# dac-shield.net
KiCad netlist of a schematic drawn in EAGLE
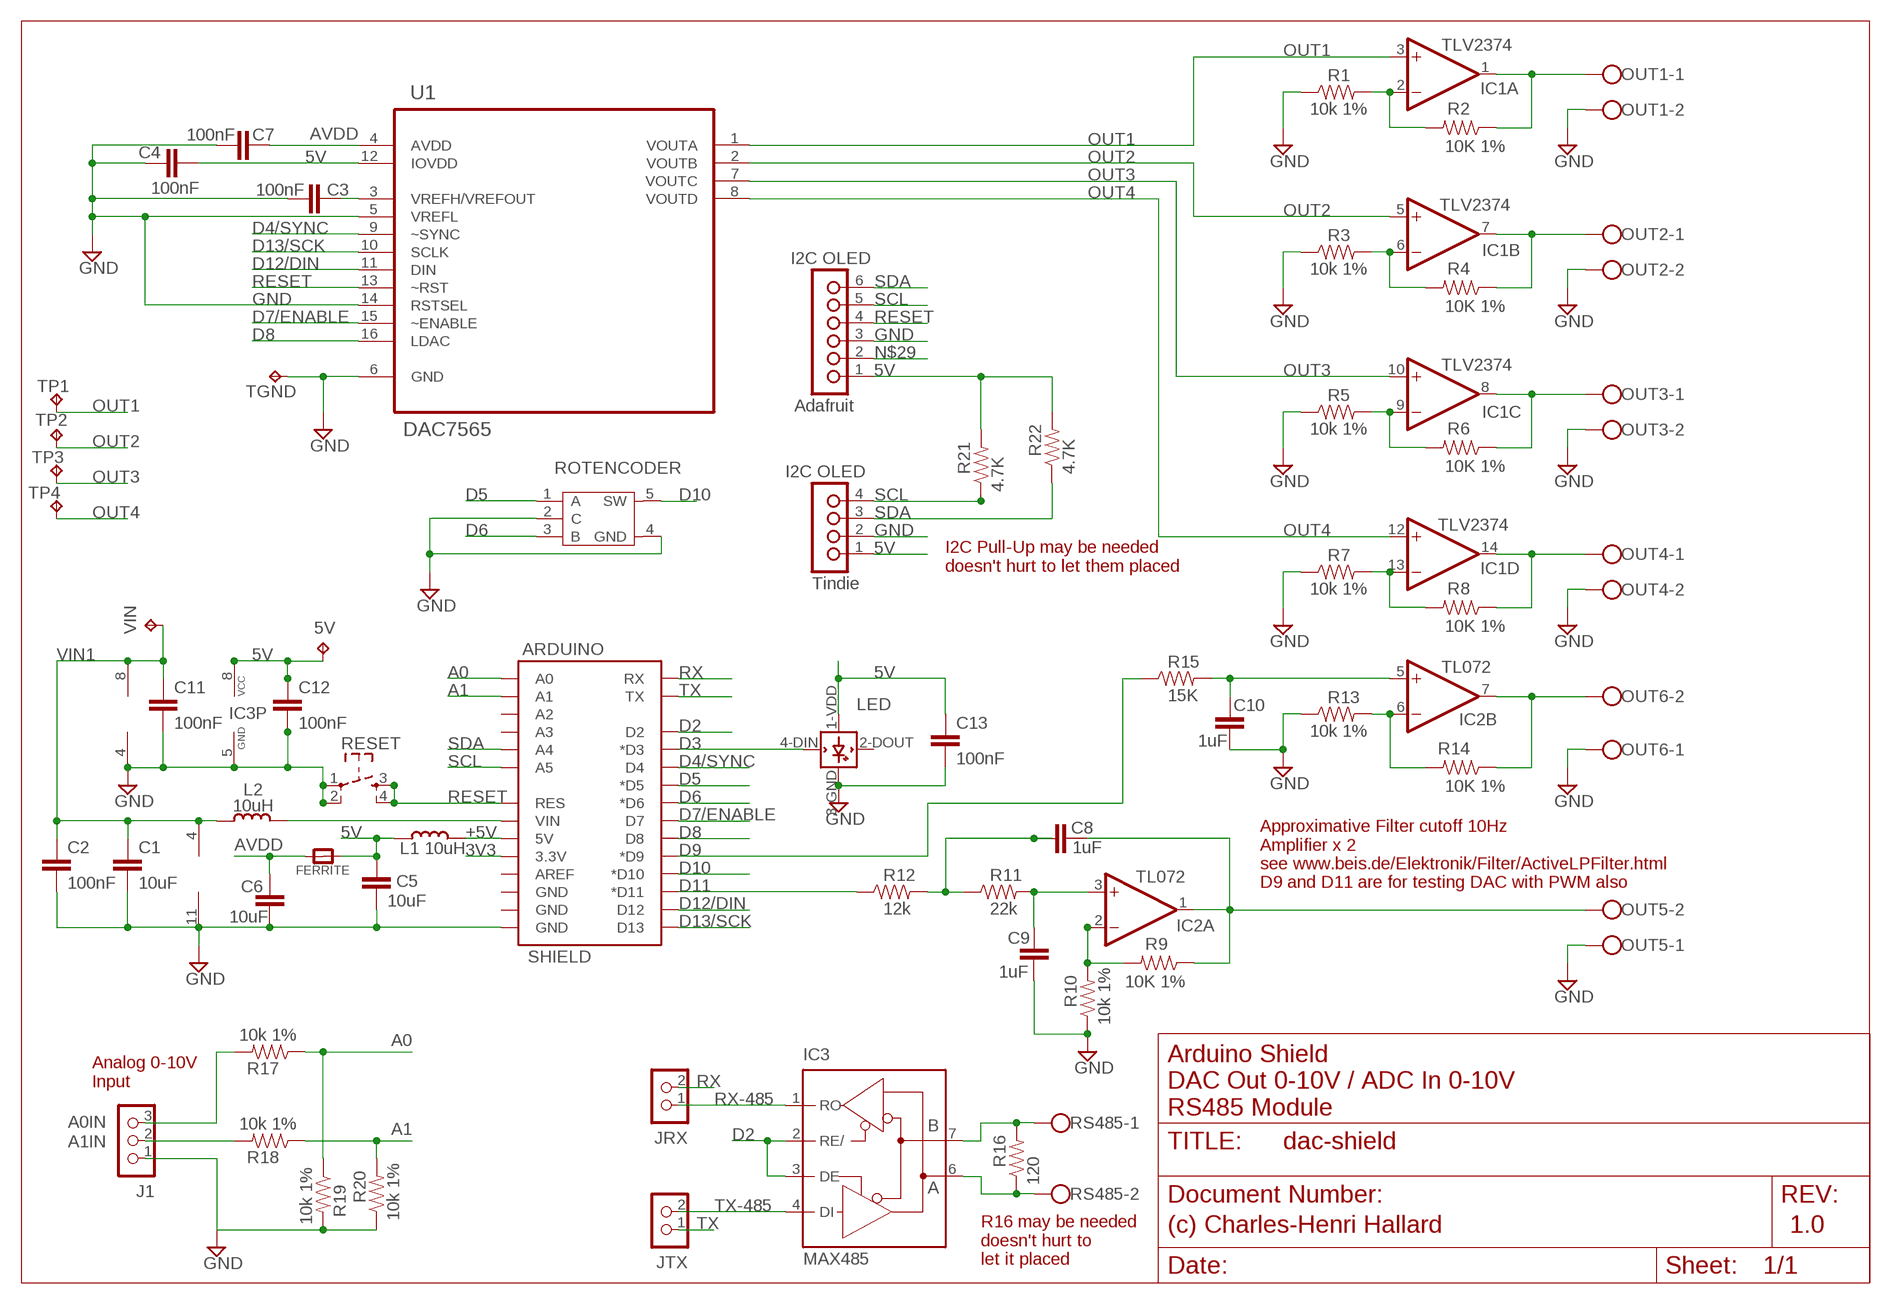
[diagram p0: schematic, sheet 1]

(export (version "E")
  (design (tool "Eeschema 10.0.6"))
  (components
    (comp (ref "5V")
      (value "TPPAD1-13")
      (footprint "eagle-import:P1-13")
      (libsource (lib "eagle-import") (part "TPPAD1-13"))
    )
    (comp (ref "ARDUINO")
      (value "SHIELD")
      (footprint "eagle-import:DUEMILANOVE_SHIELD_NOHOLES")
      (libsource (lib "eagle-import") (part "ARDUINO_SHIELDNOHOLES"))
    )
    (comp (ref "C1")
      (value "10uF")
      (footprint "eagle-import:0805-CAP")
      (libsource (lib "eagle-import") (part "CAP0805-CAP"))
    )
    (comp (ref "C2")
      (value "100nF")
      (footprint "eagle-import:0805-CAP")
      (libsource (lib "eagle-import") (part "CAP0805-CAP"))
    )
    (comp (ref "C3")
      (value "100nF")
      (footprint "eagle-import:0805-CAP")
      (libsource (lib "eagle-import") (part "CAP0805-CAP"))
    )
    (comp (ref "C4")
      (value "100nF")
      (footprint "eagle-import:0805-CAP")
      (libsource (lib "eagle-import") (part "CAP0805-CAP"))
    )
    (comp (ref "C5")
      (value "10uF")
      (footprint "eagle-import:0805-CAP")
      (libsource (lib "eagle-import") (part "CAP0805-CAP"))
    )
    (comp (ref "C6")
      (value "10uF")
      (footprint "eagle-import:0805-CAP")
      (libsource (lib "eagle-import") (part "CAP0805-CAP"))
    )
    (comp (ref "C7")
      (value "100nF")
      (footprint "eagle-import:0805-CAP")
      (libsource (lib "eagle-import") (part "CAP0805-CAP"))
    )
    (comp (ref "C8")
      (value "1uF")
      (footprint "eagle-import:0805-CAP")
      (libsource (lib "eagle-import") (part "CAP0805-CAP"))
    )
    (comp (ref "C9")
      (value "1uF")
      (footprint "eagle-import:0805-CAP")
      (libsource (lib "eagle-import") (part "CAP0805-CAP"))
    )
    (comp (ref "C10")
      (value "1uF")
      (footprint "eagle-import:0805-CAP")
      (libsource (lib "eagle-import") (part "CAP0805-CAP"))
    )
    (comp (ref "C11")
      (value "100nF")
      (footprint "eagle-import:0805-CAP")
      (libsource (lib "eagle-import") (part "CAP0805-CAP"))
    )
    (comp (ref "C12")
      (value "100nF")
      (footprint "eagle-import:0805-CAP")
      (libsource (lib "eagle-import") (part "CAP0805-CAP"))
    )
    (comp (ref "C13")
      (value "100nF")
      (footprint "eagle-import:0805-CAP")
      (libsource (lib "eagle-import") (part "CAP0805-CAP"))
    )
    (comp (ref "FERRITE")
      (value "FERRITE_0603")
      (footprint "eagle-import:_0603")
      (libsource (lib "eagle-import") (part "FERRITE_0603"))
    )
    (comp (ref "IC1")
      (value "TLV2374")
      (footprint "eagle-import:SO14")
      (libsource (lib "eagle-import") (part "LM324D"))
    )
    (comp (ref "IC2")
      (value "TL072")
      (footprint "eagle-import:SO08")
      (libsource (lib "eagle-import") (part "TL072D"))
    )
    (comp (ref "IC3")
      (value "MAX485")
      (footprint "eagle-import:SO08")
      (fields (field (name "MF") "MAXIM") (field (name "MPN") "MAX481CSA"))
      (libsource (lib "eagle-import") (part "MAX481CSA"))
    )
    (comp (ref "J1")
      (value "CON_HEADER_1X03-PTH")
      (footprint "eagle-import:M1X3")
      (libsource (lib "eagle-import") (part "CON_HEADER_1X03-PTH"))
    )
    (comp (ref "JRX")
      (value "CON_HEADER_1X02-PTH")
      (footprint "eagle-import:M1X2")
      (libsource (lib "eagle-import") (part "CON_HEADER_1X02-PTH"))
    )
    (comp (ref "JTX")
      (value "CON_HEADER_1X02-PTH")
      (footprint "eagle-import:M1X2")
      (libsource (lib "eagle-import") (part "CON_HEADER_1X02-PTH"))
    )
    (comp (ref "L1")
      (value "10uH")
      (footprint "eagle-import:_0805")
      (libsource (lib "eagle-import") (part "INDUCTOR_0805"))
    )
    (comp (ref "L2")
      (value "10uH")
      (footprint "eagle-import:_0805")
      (libsource (lib "eagle-import") (part "INDUCTOR_0805"))
    )
    (comp (ref "LED")
      (value "WS2812B")
      (footprint "eagle-import:WS2812B")
      (libsource (lib "eagle-import") (part "WS2812B"))
    )
    (comp (ref "OUT1")
      (value "CON-CLAMP-2")
      (footprint "eagle-import:W237-102")
      (libsource (lib "eagle-import") (part "CON-CLAMP-2"))
    )
    (comp (ref "OUT2")
      (value "CON-CLAMP-2")
      (footprint "eagle-import:W237-102")
      (libsource (lib "eagle-import") (part "CON-CLAMP-2"))
    )
    (comp (ref "OUT3")
      (value "CON-CLAMP-2")
      (footprint "eagle-import:W237-102")
      (libsource (lib "eagle-import") (part "CON-CLAMP-2"))
    )
    (comp (ref "OUT4")
      (value "CON-CLAMP-2")
      (footprint "eagle-import:W237-102")
      (libsource (lib "eagle-import") (part "CON-CLAMP-2"))
    )
    (comp (ref "OUT5")
      (value "CON-CLAMP-2")
      (footprint "eagle-import:W237-102")
      (libsource (lib "eagle-import") (part "CON-CLAMP-2"))
    )
    (comp (ref "OUT6")
      (value "CON-CLAMP-2")
      (footprint "eagle-import:W237-102")
      (libsource (lib "eagle-import") (part "CON-CLAMP-2"))
    )
    (comp (ref "R1")
      (value "10k 1%")
      (footprint "eagle-import:0805-RES")
      (libsource (lib "eagle-import") (part "RESISTOR0805-RES"))
    )
    (comp (ref "R2")
      (value "10K 1%")
      (footprint "eagle-import:0805-RES")
      (libsource (lib "eagle-import") (part "RESISTOR0805-RES"))
    )
    (comp (ref "R3")
      (value "10k 1%")
      (footprint "eagle-import:0805-RES")
      (libsource (lib "eagle-import") (part "RESISTOR0805-RES"))
    )
    (comp (ref "R4")
      (value "10K 1%")
      (footprint "eagle-import:0805-RES")
      (libsource (lib "eagle-import") (part "RESISTOR0805-RES"))
    )
    (comp (ref "R5")
      (value "10k 1%")
      (footprint "eagle-import:0805-RES")
      (libsource (lib "eagle-import") (part "RESISTOR0805-RES"))
    )
    (comp (ref "R6")
      (value "10K 1%")
      (footprint "eagle-import:0805-RES")
      (libsource (lib "eagle-import") (part "RESISTOR0805-RES"))
    )
    (comp (ref "R7")
      (value "10k 1%")
      (footprint "eagle-import:0805-RES")
      (libsource (lib "eagle-import") (part "RESISTOR0805-RES"))
    )
    (comp (ref "R8")
      (value "10K 1%")
      (footprint "eagle-import:0805-RES")
      (libsource (lib "eagle-import") (part "RESISTOR0805-RES"))
    )
    (comp (ref "R9")
      (value "10K 1%")
      (footprint "eagle-import:0805-RES")
      (libsource (lib "eagle-import") (part "RESISTOR0805-RES"))
    )
    (comp (ref "R10")
      (value "10k 1%")
      (footprint "eagle-import:0805-RES")
      (libsource (lib "eagle-import") (part "RESISTOR0805-RES"))
    )
    (comp (ref "R11")
      (value "22k")
      (footprint "eagle-import:0805-RES")
      (libsource (lib "eagle-import") (part "RESISTOR0805-RES"))
    )
    (comp (ref "R12")
      (value "12k")
      (footprint "eagle-import:0805-RES")
      (libsource (lib "eagle-import") (part "RESISTOR0805-RES"))
    )
    (comp (ref "R13")
      (value "10k 1%")
      (footprint "eagle-import:0805-RES")
      (libsource (lib "eagle-import") (part "RESISTOR0805-RES"))
    )
    (comp (ref "R14")
      (value "10K 1%")
      (footprint "eagle-import:0805-RES")
      (libsource (lib "eagle-import") (part "RESISTOR0805-RES"))
    )
    (comp (ref "R15")
      (value "15K")
      (footprint "eagle-import:0805-RES")
      (libsource (lib "eagle-import") (part "RESISTOR0805-RES"))
    )
    (comp (ref "R16")
      (value "120")
      (footprint "eagle-import:0805-RES")
      (libsource (lib "eagle-import") (part "RESISTOR0805-RES"))
    )
    (comp (ref "R17")
      (value "10k 1%")
      (footprint "eagle-import:0805-RES")
      (libsource (lib "eagle-import") (part "RESISTOR0805-RES"))
    )
    (comp (ref "R18")
      (value "10k 1%")
      (footprint "eagle-import:0805-RES")
      (libsource (lib "eagle-import") (part "RESISTOR0805-RES"))
    )
    (comp (ref "R19")
      (value "10k 1%")
      (footprint "eagle-import:0805-RES")
      (libsource (lib "eagle-import") (part "RESISTOR0805-RES"))
    )
    (comp (ref "R20")
      (value "10k 1%")
      (footprint "eagle-import:0805-RES")
      (libsource (lib "eagle-import") (part "RESISTOR0805-RES"))
    )
    (comp (ref "R21")
      (value "4.7K")
      (footprint "eagle-import:0805-RES")
      (libsource (lib "eagle-import") (part "RESISTOR0805-RES"))
    )
    (comp (ref "R22")
      (value "4.7K")
      (footprint "eagle-import:0805-RES")
      (libsource (lib "eagle-import") (part "RESISTOR0805-RES"))
    )
    (comp (ref "RESET")
      (value "SW_TACT_4P")
      (footprint "eagle-import:SW_TACT_SMALL")
      (libsource (lib "eagle-import") (part "SW_TACT_4P"))
    )
    (comp (ref "ROTENCODER")
      (value "ROTARY-ENCODE-5P")
      (footprint "eagle-import:5P-13.75X11.7X6.5H")
      (libsource (lib "eagle-import") (part "ROTARY-ENCODE-5P"))
    )
    (comp (ref "RS485")
      (value "CON-CLAMP-2")
      (footprint "eagle-import:W237-102")
      (libsource (lib "eagle-import") (part "CON-CLAMP-2"))
    )
    (comp (ref "TGND")
      (value "TPPAD1-13")
      (footprint "eagle-import:P1-13")
      (libsource (lib "eagle-import") (part "TPPAD1-13"))
    )
    (comp (ref "TP1")
      (value "TPPAD1-13")
      (footprint "eagle-import:P1-13")
      (libsource (lib "eagle-import") (part "TPPAD1-13"))
    )
    (comp (ref "TP2")
      (value "TPPAD1-13")
      (footprint "eagle-import:P1-13")
      (libsource (lib "eagle-import") (part "TPPAD1-13"))
    )
    (comp (ref "TP3")
      (value "TPPAD1-13")
      (footprint "eagle-import:P1-13")
      (libsource (lib "eagle-import") (part "TPPAD1-13"))
    )
    (comp (ref "TP4")
      (value "TPPAD1-13")
      (footprint "eagle-import:P1-13")
      (libsource (lib "eagle-import") (part "TPPAD1-13"))
    )
    (comp (ref "U$1")
      (value "OLED_I2C_ADAFRUIT")
      (footprint "eagle-import:1X06_LOCK")
      (libsource (lib "eagle-import") (part "OLED_I2C_ADAFRUIT"))
    )
    (comp (ref "U$2")
      (value "OLED_I2C_TINDIE")
      (footprint "eagle-import:1X04_LOCK")
      (libsource (lib "eagle-import") (part "OLED_I2C_TINDIE"))
    )
    (comp (ref "U1")
      (value "DAC7565")
      (footprint "eagle-import:SOP65P640X120-16N")
      (fields (field (name "MPN") "DAC7565IAPW"))
      (libsource (lib "eagle-import") (part "DAC7565IAPW"))
    )
    (comp (ref "VIN")
      (value "TPPAD1-13")
      (footprint "eagle-import:P1-13")
      (libsource (lib "eagle-import") (part "TPPAD1-13"))
    )
  )
  (nets
    (net (code "1") (name "/+5V") (class "Default")
      (node (ref "ARDUINO") (pin "5V") (pinfunction "5V_5V") (pintype "bidirectional"))
      (node (ref "L1") (pin "2") (pinfunction "2_2") (pintype "passive"))
    )
    (net (code "2") (name "/3V3") (class "Default")
      (node (ref "ARDUINO") (pin "3.3V") (pinfunction "3.3V_3.3V") (pintype "bidirectional"))
    )
    (net (code "3") (name "/5V") (class "Default")
      (node (ref "5V") (pin "TP") (pinfunction "TP_TP") (pintype "input"))
      (node (ref "C12") (pin "1") (pinfunction "1_1") (pintype "passive"))
      (node (ref "C13") (pin "1") (pinfunction "1_1") (pintype "passive"))
      (node (ref "C4") (pin "1") (pinfunction "1_1") (pintype "passive"))
      (node (ref "C5") (pin "1") (pinfunction "1_1") (pintype "passive"))
      (node (ref "FERRITE") (pin "1") (pinfunction "P$1_1") (pintype "passive"))
      (node (ref "IC3") (pin "8") (pinfunction "VCC_8") (pintype "power_in"))
      (node (ref "L1") (pin "1") (pinfunction "1_1") (pintype "passive"))
      (node (ref "LED") (pin "1-VDD") (pinfunction "VDD_1-VDD") (pintype "bidirectional"))
      (node (ref "R21") (pin "2") (pinfunction "2_2") (pintype "passive"))
      (node (ref "R22") (pin "2") (pinfunction "2_2") (pintype "passive"))
      (node (ref "U$1") (pin "1") (pinfunction "VIN_1") (pintype "power_in"))
      (node (ref "U$2") (pin "1") (pinfunction "VCC_1") (pintype "power_in"))
      (node (ref "U1") (pin "12") (pinfunction "IOVDD_12") (pintype "power_in"))
    )
    (net (code "4") (name "/A0") (class "Default")
      (node (ref "ARDUINO") (pin "A0") (pinfunction "A0_A0") (pintype "bidirectional"))
      (node (ref "R17") (pin "1") (pinfunction "1_1") (pintype "passive"))
      (node (ref "R19") (pin "1") (pinfunction "1_1") (pintype "passive"))
    )
    (net (code "5") (name "/A0IN") (class "Default")
      (node (ref "J1") (pin "3") (pinfunction "3_3") (pintype "bidirectional"))
      (node (ref "R17") (pin "2") (pinfunction "2_2") (pintype "passive"))
    )
    (net (code "6") (name "/A1") (class "Default")
      (node (ref "ARDUINO") (pin "A1") (pinfunction "A1_A1") (pintype "bidirectional"))
      (node (ref "R18") (pin "1") (pinfunction "1_1") (pintype "passive"))
      (node (ref "R20") (pin "2") (pinfunction "2_2") (pintype "passive"))
    )
    (net (code "7") (name "/A1IN") (class "Default")
      (node (ref "J1") (pin "2") (pinfunction "2_2") (pintype "bidirectional"))
      (node (ref "R18") (pin "2") (pinfunction "2_2") (pintype "passive"))
    )
    (net (code "8") (name "/AVDD") (class "Default")
      (node (ref "C6") (pin "2") (pinfunction "2_2") (pintype "passive"))
      (node (ref "C7") (pin "1") (pinfunction "1_1") (pintype "passive"))
      (node (ref "FERRITE") (pin "2") (pinfunction "P$2_2") (pintype "passive"))
      (node (ref "U1") (pin "4") (pinfunction "AVDD_4") (pintype "power_in"))
    )
    (net (code "9") (name "/D2") (class "Default")
      (node (ref "ARDUINO") (pin "D2") (pinfunction "D2_D2") (pintype "bidirectional"))
      (node (ref "IC3") (pin "2") (pinfunction "RE/_2") (pintype "input"))
      (node (ref "IC3") (pin "3") (pinfunction "DE_3") (pintype "input"))
    )
    (net (code "10") (name "/D3") (class "Default")
      (node (ref "ARDUINO") (pin "D3") (pinfunction "*D3_D3") (pintype "bidirectional"))
      (node (ref "LED") (pin "4-DIN") (pinfunction "DIN_4-DIN") (pintype "input"))
    )
    (net (code "11") (name "/D4{slash}SYNC") (class "Default")
      (node (ref "ARDUINO") (pin "D4") (pinfunction "D4_D4") (pintype "bidirectional"))
      (node (ref "U1") (pin "9") (pinfunction "~{SYNC}_9") (pintype "input"))
    )
    (net (code "12") (name "/D5") (class "Default")
      (node (ref "ARDUINO") (pin "D5") (pinfunction "*D5_D5") (pintype "bidirectional"))
      (node (ref "ROTENCODER") (pin "1") (pinfunction "A_1") (pintype "bidirectional"))
    )
    (net (code "13") (name "/D6") (class "Default")
      (node (ref "ARDUINO") (pin "D6") (pinfunction "*D6_D6") (pintype "bidirectional"))
      (node (ref "ROTENCODER") (pin "3") (pinfunction "B_3") (pintype "bidirectional"))
    )
    (net (code "14") (name "/D7{slash}ENABLE") (class "Default")
      (node (ref "ARDUINO") (pin "D7") (pinfunction "D7_D7") (pintype "bidirectional"))
      (node (ref "U1") (pin "15") (pinfunction "~{ENABLE}_15") (pintype "input"))
    )
    (net (code "15") (name "/D8") (class "Default")
      (node (ref "ARDUINO") (pin "D8") (pinfunction "D8_D8") (pintype "bidirectional"))
      (node (ref "U1") (pin "16") (pinfunction "LDAC_16") (pintype "input"))
    )
    (net (code "16") (name "/D9") (class "Default")
      (node (ref "ARDUINO") (pin "D9") (pinfunction "*D9_D9") (pintype "bidirectional"))
      (node (ref "R15") (pin "1") (pinfunction "1_1") (pintype "passive"))
    )
    (net (code "17") (name "/D10") (class "Default")
      (node (ref "ARDUINO") (pin "D10") (pinfunction "*D10_D10") (pintype "bidirectional"))
      (node (ref "ROTENCODER") (pin "5") (pinfunction "SW_5") (pintype "bidirectional"))
    )
    (net (code "18") (name "/D11") (class "Default")
      (node (ref "ARDUINO") (pin "D11") (pinfunction "*D11_D11") (pintype "bidirectional"))
      (node (ref "R12") (pin "1") (pinfunction "1_1") (pintype "passive"))
    )
    (net (code "19") (name "/D12{slash}DIN") (class "Default")
      (node (ref "ARDUINO") (pin "D12") (pinfunction "D12_D12") (pintype "bidirectional"))
      (node (ref "U1") (pin "11") (pinfunction "DIN_11") (pintype "input"))
    )
    (net (code "20") (name "/D13{slash}SCK") (class "Default")
      (node (ref "ARDUINO") (pin "D13") (pinfunction "D13_D13") (pintype "bidirectional"))
      (node (ref "U1") (pin "10") (pinfunction "SCLK_10") (pintype "input"))
    )
    (net (code "21") (name "/N$29") (class "Default")
      (node (ref "U$1") (pin "2") (pinfunction "3V3_2") (pintype "output"))
    )
    (net (code "22") (name "/OUT1") (class "Default")
      (node (ref "IC1") (pin "3") (pinfunction "+IN_3") (pintype "input"))
      (node (ref "TP1") (pin "TP") (pinfunction "TP_TP") (pintype "input"))
      (node (ref "U1") (pin "1") (pinfunction "VOUTA_1") (pintype "output"))
    )
    (net (code "23") (name "/OUT2") (class "Default")
      (node (ref "IC1") (pin "5") (pinfunction "+IN_5") (pintype "input"))
      (node (ref "TP2") (pin "TP") (pinfunction "TP_TP") (pintype "input"))
      (node (ref "U1") (pin "2") (pinfunction "VOUTB_2") (pintype "output"))
    )
    (net (code "24") (name "/OUT3") (class "Default")
      (node (ref "IC1") (pin "10") (pinfunction "+IN_10") (pintype "input"))
      (node (ref "TP3") (pin "TP") (pinfunction "TP_TP") (pintype "input"))
      (node (ref "U1") (pin "7") (pinfunction "VOUTC_7") (pintype "output"))
    )
    (net (code "25") (name "/OUT4") (class "Default")
      (node (ref "IC1") (pin "12") (pinfunction "+IN_12") (pintype "input"))
      (node (ref "TP4") (pin "TP") (pinfunction "TP_TP") (pintype "input"))
      (node (ref "U1") (pin "8") (pinfunction "VOUTD_8") (pintype "output"))
    )
    (net (code "26") (name "/RESET") (class "Default")
      (node (ref "ARDUINO") (pin "RES") (pinfunction "RES_RES") (pintype "bidirectional"))
      (node (ref "RESET") (pin "3") (pinfunction "3_3") (pintype "passive"))
      (node (ref "RESET") (pin "4") (pinfunction "4_4") (pintype "passive"))
      (node (ref "U$1") (pin "4") (pinfunction "RST_4") (pintype "input"))
      (node (ref "U1") (pin "13") (pinfunction "~{RST}_13") (pintype "input"))
    )
    (net (code "27") (name "/RX") (class "Default")
      (node (ref "ARDUINO") (pin "RX") (pinfunction "RX_RX") (pintype "bidirectional"))
      (node (ref "JRX") (pin "2") (pinfunction "2_2") (pintype "passive"))
    )
    (net (code "28") (name "/RX-485") (class "Default")
      (node (ref "IC3") (pin "1") (pinfunction "RO_1") (pintype "output"))
      (node (ref "JRX") (pin "1") (pinfunction "1_1") (pintype "passive"))
    )
    (net (code "29") (name "/SCL") (class "Default")
      (node (ref "ARDUINO") (pin "A5") (pinfunction "A5_A5") (pintype "bidirectional"))
      (node (ref "R21") (pin "1") (pinfunction "1_1") (pintype "passive"))
      (node (ref "U$1") (pin "5") (pinfunction "SCL_5") (pintype "bidirectional"))
      (node (ref "U$2") (pin "4") (pinfunction "SCL_4") (pintype "bidirectional"))
    )
    (net (code "30") (name "/SDA") (class "Default")
      (node (ref "ARDUINO") (pin "A4") (pinfunction "A4_A4") (pintype "bidirectional"))
      (node (ref "R22") (pin "1") (pinfunction "1_1") (pintype "passive"))
      (node (ref "U$1") (pin "6") (pinfunction "SDA_6") (pintype "bidirectional"))
      (node (ref "U$2") (pin "3") (pinfunction "SDA_3") (pintype "bidirectional"))
    )
    (net (code "31") (name "/TX") (class "Default")
      (node (ref "ARDUINO") (pin "TX") (pinfunction "TX_TX") (pintype "bidirectional"))
      (node (ref "JTX") (pin "1") (pinfunction "1_1") (pintype "passive"))
    )
    (net (code "32") (name "/TX-485") (class "Default")
      (node (ref "IC3") (pin "4") (pinfunction "DI_4") (pintype "input"))
      (node (ref "JTX") (pin "2") (pinfunction "2_2") (pintype "passive"))
    )
    (net (code "33") (name "/VIN1") (class "Default")
      (node (ref "C1") (pin "1") (pinfunction "1_1") (pintype "passive"))
      (node (ref "C11") (pin "1") (pinfunction "1_1") (pintype "passive"))
      (node (ref "C2") (pin "1") (pinfunction "1_1") (pintype "passive"))
      (node (ref "IC1") (pin "4") (pinfunction "V+_4") (pintype "power_in"))
      (node (ref "IC2") (pin "8") (pinfunction "V+_8") (pintype "power_in"))
      (node (ref "L2") (pin "1") (pinfunction "1_1") (pintype "passive"))
      (node (ref "VIN") (pin "TP") (pinfunction "TP_TP") (pintype "input"))
    )
    (net (code "34") (name "GND") (class "Default")
      (node (ref "ARDUINO") (pin "GND@0") (pinfunction "GND_GND@0") (pintype "bidirectional"))
      (node (ref "C1") (pin "2") (pinfunction "2_2") (pintype "passive"))
      (node (ref "C10") (pin "1") (pinfunction "1_1") (pintype "passive"))
      (node (ref "C11") (pin "2") (pinfunction "2_2") (pintype "passive"))
      (node (ref "C12") (pin "2") (pinfunction "2_2") (pintype "passive"))
      (node (ref "C13") (pin "2") (pinfunction "2_2") (pintype "passive"))
      (node (ref "C2") (pin "2") (pinfunction "2_2") (pintype "passive"))
      (node (ref "C3") (pin "2") (pinfunction "2_2") (pintype "passive"))
      (node (ref "C4") (pin "2") (pinfunction "2_2") (pintype "passive"))
      (node (ref "C5") (pin "2") (pinfunction "2_2") (pintype "passive"))
      (node (ref "C6") (pin "1") (pinfunction "1_1") (pintype "passive"))
      (node (ref "C7") (pin "2") (pinfunction "2_2") (pintype "passive"))
      (node (ref "C9") (pin "1") (pinfunction "1_1") (pintype "passive"))
      (node (ref "IC1") (pin "11") (pinfunction "V-_11") (pintype "power_in"))
      (node (ref "IC2") (pin "4") (pinfunction "V-_4") (pintype "power_in"))
      (node (ref "IC3") (pin "5") (pinfunction "GND_5") (pintype "power_in"))
      (node (ref "J1") (pin "1") (pinfunction "1_1") (pintype "bidirectional"))
      (node (ref "LED") (pin "3-GND") (pinfunction "GND_3-GND") (pintype "bidirectional"))
      (node (ref "OUT1") (pin "2") (pinfunction "KL_2") (pintype "passive"))
      (node (ref "OUT2") (pin "2") (pinfunction "KL_2") (pintype "passive"))
      (node (ref "OUT3") (pin "2") (pinfunction "KL_2") (pintype "passive"))
      (node (ref "OUT4") (pin "2") (pinfunction "KL_2") (pintype "passive"))
      (node (ref "OUT5") (pin "1") (pinfunction "KL_1") (pintype "passive"))
      (node (ref "OUT6") (pin "1") (pinfunction "KL_1") (pintype "passive"))
      (node (ref "R1") (pin "1") (pinfunction "1_1") (pintype "passive"))
      (node (ref "R10") (pin "1") (pinfunction "1_1") (pintype "passive"))
      (node (ref "R13") (pin "1") (pinfunction "1_1") (pintype "passive"))
      (node (ref "R19") (pin "2") (pinfunction "2_2") (pintype "passive"))
      (node (ref "R20") (pin "1") (pinfunction "1_1") (pintype "passive"))
      (node (ref "R3") (pin "1") (pinfunction "1_1") (pintype "passive"))
      (node (ref "R5") (pin "1") (pinfunction "1_1") (pintype "passive"))
      (node (ref "R7") (pin "1") (pinfunction "1_1") (pintype "passive"))
      (node (ref "RESET") (pin "1") (pinfunction "1_1") (pintype "passive"))
      (node (ref "RESET") (pin "2") (pinfunction "2_2") (pintype "passive"))
      (node (ref "ROTENCODER") (pin "2") (pinfunction "C_2") (pintype "bidirectional"))
      (node (ref "ROTENCODER") (pin "4") (pinfunction "GND_4") (pintype "bidirectional"))
      (node (ref "TGND") (pin "TP") (pinfunction "TP_TP") (pintype "input"))
      (node (ref "U$1") (pin "3") (pinfunction "GND_3") (pintype "passive"))
      (node (ref "U$2") (pin "2") (pinfunction "GND_2") (pintype "power_in"))
      (node (ref "U1") (pin "14") (pinfunction "RSTSEL_14") (pintype "input"))
      (node (ref "U1") (pin "5") (pinfunction "VREFL_5") (pintype "input"))
      (node (ref "U1") (pin "6") (pinfunction "GND_6") (pintype "passive"))
    )
    (net (code "35") (name "Net-(ARDUINO-PadVIN)") (class "Default")
      (node (ref "ARDUINO") (pin "VIN") (pinfunction "VIN_VIN") (pintype "bidirectional"))
      (node (ref "L2") (pin "2") (pinfunction "2_2") (pintype "passive"))
    )
    (net (code "36") (name "Net-(C8-Pad1)") (class "Default")
      (node (ref "C8") (pin "1") (pinfunction "1_1") (pintype "passive"))
      (node (ref "R11") (pin "1") (pinfunction "1_1") (pintype "passive"))
      (node (ref "R12") (pin "2") (pinfunction "2_2") (pintype "passive"))
    )
    (net (code "37") (name "Net-(IC1A--IN)") (class "Default")
      (node (ref "IC1") (pin "2") (pinfunction "-IN_2") (pintype "input"))
      (node (ref "R1") (pin "2") (pinfunction "2_2") (pintype "passive"))
      (node (ref "R2") (pin "2") (pinfunction "2_2") (pintype "passive"))
    )
    (net (code "38") (name "Net-(IC1A-OUT)") (class "Default")
      (node (ref "IC1") (pin "1") (pinfunction "OUT_1") (pintype "output"))
      (node (ref "OUT1") (pin "1") (pinfunction "KL_1") (pintype "passive"))
      (node (ref "R2") (pin "1") (pinfunction "1_1") (pintype "passive"))
    )
    (net (code "39") (name "Net-(IC1B--IN)") (class "Default")
      (node (ref "IC1") (pin "6") (pinfunction "-IN_6") (pintype "input"))
      (node (ref "R3") (pin "2") (pinfunction "2_2") (pintype "passive"))
      (node (ref "R4") (pin "2") (pinfunction "2_2") (pintype "passive"))
    )
    (net (code "40") (name "Net-(IC1B-OUT)") (class "Default")
      (node (ref "IC1") (pin "7") (pinfunction "OUT_7") (pintype "output"))
      (node (ref "OUT2") (pin "1") (pinfunction "KL_1") (pintype "passive"))
      (node (ref "R4") (pin "1") (pinfunction "1_1") (pintype "passive"))
    )
    (net (code "41") (name "Net-(IC1C--IN)") (class "Default")
      (node (ref "IC1") (pin "9") (pinfunction "-IN_9") (pintype "input"))
      (node (ref "R5") (pin "2") (pinfunction "2_2") (pintype "passive"))
      (node (ref "R6") (pin "2") (pinfunction "2_2") (pintype "passive"))
    )
    (net (code "42") (name "Net-(IC1C-OUT)") (class "Default")
      (node (ref "IC1") (pin "8") (pinfunction "OUT_8") (pintype "output"))
      (node (ref "OUT3") (pin "1") (pinfunction "KL_1") (pintype "passive"))
      (node (ref "R6") (pin "1") (pinfunction "1_1") (pintype "passive"))
    )
    (net (code "43") (name "Net-(IC1D--IN)") (class "Default")
      (node (ref "IC1") (pin "13") (pinfunction "-IN_13") (pintype "input"))
      (node (ref "R7") (pin "2") (pinfunction "2_2") (pintype "passive"))
      (node (ref "R8") (pin "2") (pinfunction "2_2") (pintype "passive"))
    )
    (net (code "44") (name "Net-(IC1D-OUT)") (class "Default")
      (node (ref "IC1") (pin "14") (pinfunction "OUT_14") (pintype "output"))
      (node (ref "OUT4") (pin "1") (pinfunction "KL_1") (pintype "passive"))
      (node (ref "R8") (pin "1") (pinfunction "1_1") (pintype "passive"))
    )
    (net (code "45") (name "Net-(IC2A-+IN)") (class "Default")
      (node (ref "C9") (pin "2") (pinfunction "2_2") (pintype "passive"))
      (node (ref "IC2") (pin "3") (pinfunction "+IN_3") (pintype "input"))
      (node (ref "R11") (pin "2") (pinfunction "2_2") (pintype "passive"))
    )
    (net (code "46") (name "Net-(IC2A--IN)") (class "Default")
      (node (ref "IC2") (pin "2") (pinfunction "-IN_2") (pintype "input"))
      (node (ref "R10") (pin "2") (pinfunction "2_2") (pintype "passive"))
      (node (ref "R9") (pin "2") (pinfunction "2_2") (pintype "passive"))
    )
    (net (code "47") (name "Net-(IC2A-OUT)") (class "Default")
      (node (ref "C8") (pin "2") (pinfunction "2_2") (pintype "passive"))
      (node (ref "IC2") (pin "1") (pinfunction "OUT_1") (pintype "output"))
      (node (ref "OUT5") (pin "2") (pinfunction "KL_2") (pintype "passive"))
      (node (ref "R9") (pin "1") (pinfunction "1_1") (pintype "passive"))
    )
    (net (code "48") (name "Net-(IC2B-+IN)") (class "Default")
      (node (ref "C10") (pin "2") (pinfunction "2_2") (pintype "passive"))
      (node (ref "IC2") (pin "5") (pinfunction "+IN_5") (pintype "input"))
      (node (ref "R15") (pin "2") (pinfunction "2_2") (pintype "passive"))
    )
    (net (code "49") (name "Net-(IC2B--IN)") (class "Default")
      (node (ref "IC2") (pin "6") (pinfunction "-IN_6") (pintype "input"))
      (node (ref "R13") (pin "2") (pinfunction "2_2") (pintype "passive"))
      (node (ref "R14") (pin "2") (pinfunction "2_2") (pintype "passive"))
    )
    (net (code "50") (name "Net-(IC2B-OUT)") (class "Default")
      (node (ref "IC2") (pin "7") (pinfunction "OUT_7") (pintype "output"))
      (node (ref "OUT6") (pin "2") (pinfunction "KL_2") (pintype "passive"))
      (node (ref "R14") (pin "1") (pinfunction "1_1") (pintype "passive"))
    )
    (net (code "51") (name "Net-(IC3A-A)") (class "Default")
      (node (ref "IC3") (pin "6") (pinfunction "A_6") (pintype "passive"))
      (node (ref "R16") (pin "1") (pinfunction "1_1") (pintype "passive"))
      (node (ref "RS485") (pin "2") (pinfunction "KL_2") (pintype "passive"))
    )
    (net (code "52") (name "Net-(IC3A-B)") (class "Default")
      (node (ref "IC3") (pin "7") (pinfunction "B_7") (pintype "passive"))
      (node (ref "R16") (pin "2") (pinfunction "2_2") (pintype "passive"))
      (node (ref "RS485") (pin "1") (pinfunction "KL_1") (pintype "passive"))
    )
    (net (code "53") (name "Net-(U1-VREFH{slash}VREFOUT)") (class "Default")
      (node (ref "C3") (pin "1") (pinfunction "1_1") (pintype "passive"))
      (node (ref "U1") (pin "3") (pinfunction "VREFH/VREFOUT_3") (pintype "bidirectional"))
    )
    (net (code "54") (name "unconnected-(ARDUINO-GND-PadGND@1)") (class "Default")
      (node (ref "ARDUINO") (pin "GND@1") (pinfunction "GND_GND@1") (pintype "bidirectional"))
    )
    (net (code "55") (name "unconnected-(ARDUINO-GND-PadGND@2)") (class "Default")
      (node (ref "ARDUINO") (pin "GND@2") (pinfunction "GND_GND@2") (pintype "bidirectional"))
    )
    (net (code "56") (name "unconnected-(ARDUINO-PadA2)") (class "Default")
      (node (ref "ARDUINO") (pin "A2") (pinfunction "A2_A2") (pintype "bidirectional"))
    )
    (net (code "57") (name "unconnected-(ARDUINO-PadA3)") (class "Default")
      (node (ref "ARDUINO") (pin "A3") (pinfunction "A3_A3") (pintype "bidirectional"))
    )
    (net (code "58") (name "unconnected-(ARDUINO-PadAREF)") (class "Default")
      (node (ref "ARDUINO") (pin "AREF") (pinfunction "AREF_AREF") (pintype "bidirectional"))
    )
    (net (code "59") (name "unconnected-(LED-DOUT-Pad2-DOUT)") (class "Default")
      (node (ref "LED") (pin "2-DOUT") (pinfunction "DOUT_2-DOUT") (pintype "output"))
    )
  )
)
